# UART.net
KiCad netlist of a schematic drawn in Altium Designer
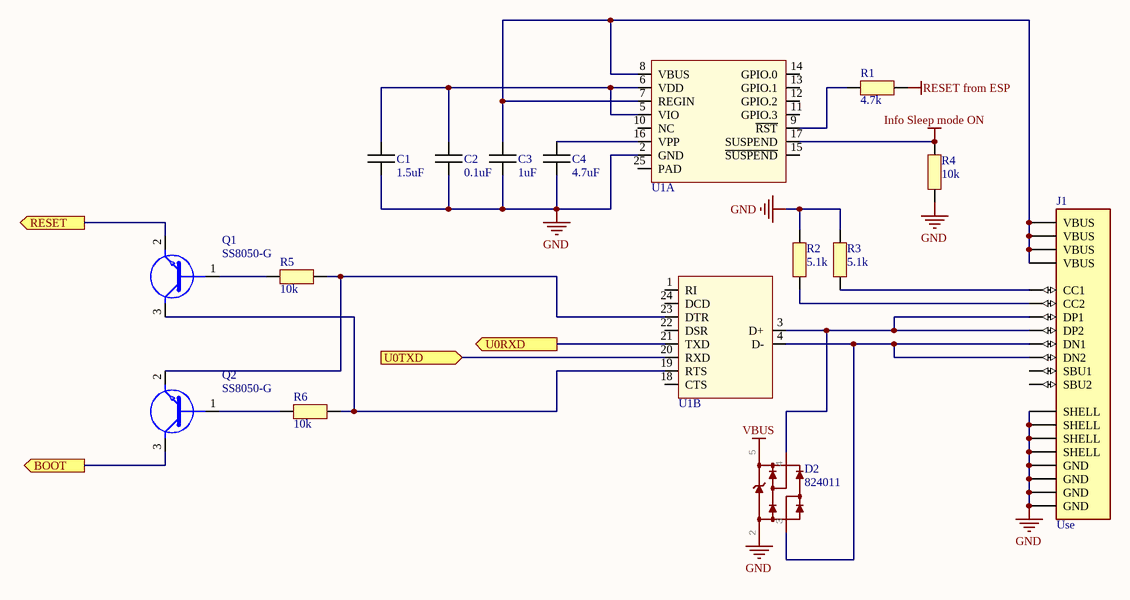
[diagram p0: UART.SchDoc]

(export (version "E")
  (design (tool "Eeschema 10.0.6"))
  (components
    (comp (ref "C1")
      (value "1.5uF")
      (footprint "CAPC1005X06N")
      (libsource (lib "SCHLibrary") (part "Capacitor"))
    )
    (comp (ref "C2")
      (value "0.1uF")
      (footprint "CAPC1005X06N")
      (libsource (lib "SCHLibrary") (part "Capacitor"))
    )
    (comp (ref "C3")
      (value "1uF")
      (footprint "CAPC1005X06N")
      (libsource (lib "SCHLibrary") (part "Capacitor"))
    )
    (comp (ref "C4")
      (value "4.7uF")
      (footprint "CAPC1005X06N")
      (libsource (lib "SCHLibrary") (part "Capacitor"))
    )
    (comp (ref "D2") (value "824011") (footprint "824011") (libsource (lib "SCHLibrary") (part "824011")))
    (comp (ref "J1")
      (value "Use")
      (footprint "USB4085-GF-A")
      (description "Connecteurs USB USB Type C, 2.0, Rec, TH , G/F, RA , Top Mnt, T & R")
      (libsource (lib "SCHLibrary") (part "USB4085-GF-A"))
    )
    (comp (ref "Q1")
      (value "SS8050-G")
      (footprint "SS8050-G")
      (description "Bipolar Transistors - BJT NPN TRANSISTOR 1.5A 40V")
      (libsource (lib "SCHLibrary") (part "SS8050-G"))
    )
    (comp (ref "Q2")
      (value "SS8050-G")
      (footprint "SS8050-G")
      (description "Bipolar Transistors - BJT NPN TRANSISTOR 1.5A 40V")
      (libsource (lib "SCHLibrary") (part "SS8050-G"))
    )
    (comp (ref "R1") (value "4.7k") (footprint "RESC1005X06N") (libsource (lib "") (part "Resistor_1")))
    (comp (ref "R2")
      (value "5.1k")
      (footprint "RESC1005X06N")
      (libsource (lib "SCHLibrary") (part "Resistor"))
    )
    (comp (ref "R3")
      (value "5.1k")
      (footprint "RESC1005X06N")
      (libsource (lib "SCHLibrary") (part "Resistor"))
    )
    (comp (ref "R4") (value "10k") (footprint "RESC1005X06N") (libsource (lib "") (part "Resistor_2")))
    (comp (ref "R5") (value "10k") (footprint "RESC1005X06N") (libsource (lib "") (part "Resistor_1")))
    (comp (ref "R6") (value "10k") (footprint "RESC1005X06N") (libsource (lib "") (part "Resistor_1")))
    (comp (ref "U1")
      (value "CP2104-F03-GM")
      (footprint "PQFN50P400X400X80_HS-25N")
      (description "USB Bridge, USB to UART USB 2.0 UART Interface 24-QFN (4x4)")
      (libsource (lib "SCHLibrary") (part "USBBridge"))
    )
  )
  (nets
    (net (code "1") (name "/BOOT") (class "Default")
      (node (ref "Q2") (pin "3") (pinfunction "C_3") (pintype "passive"))
    )
    (net (code "2") (name "/RESET") (class "Default")
      (node (ref "Q1") (pin "2") (pinfunction "E_2") (pintype "passive"))
    )
    (net (code "3") (name "/U0RXD") (class "Default")
      (node (ref "U1") (pin "21") (pinfunction "TXD_21") (pintype "passive"))
    )
    (net (code "4") (name "/U0TXD") (class "Default")
      (node (ref "U1") (pin "20") (pinfunction "RXD_20") (pintype "passive"))
    )
    (net (code "5") (name "GND") (class "Default")
      (node (ref "C1") (pin "2") (pinfunction "2_2") (pintype "passive"))
      (node (ref "C2") (pin "2") (pinfunction "2_2") (pintype "passive"))
      (node (ref "C3") (pin "2") (pinfunction "2_2") (pintype "passive"))
      (node (ref "C4") (pin "2") (pinfunction "2_2") (pintype "passive"))
      (node (ref "D2") (pin "2") (pinfunction "GND_2") (pintype "power_in"))
      (node (ref "J1") (pin "A1") (pinfunction "GND_A1") (pintype "power_in"))
      (node (ref "J1") (pin "A12") (pinfunction "GND_A12") (pintype "power_in"))
      (node (ref "J1") (pin "B1") (pinfunction "GND_B1") (pintype "power_in"))
      (node (ref "J1") (pin "B12") (pinfunction "GND_B12") (pintype "power_in"))
      (node (ref "J1") (pin "S1") (pinfunction "SHELL_S1") (pintype "passive"))
      (node (ref "J1") (pin "S2") (pinfunction "SHELL_S2") (pintype "passive"))
      (node (ref "J1") (pin "S3") (pinfunction "SHELL_S3") (pintype "passive"))
      (node (ref "J1") (pin "S4") (pinfunction "SHELL_S4") (pintype "passive"))
      (node (ref "R2") (pin "2") (pinfunction "2_2") (pintype "passive"))
      (node (ref "R3") (pin "2") (pinfunction "2_2") (pintype "passive"))
      (node (ref "R4") (pin "2") (pinfunction "2_2") (pintype "passive"))
      (node (ref "U1") (pin "2") (pinfunction "GND_2") (pintype "passive"))
    )
    (net (code "6") (name "Info Sleep mode ON") (class "Default")
      (node (ref "R4") (pin "1") (pinfunction "1_1") (pintype "passive"))
      (node (ref "U1") (pin "17") (pinfunction "SUSPEND_17") (pintype "passive"))
    )
    (net (code "7") (name "Net-(D2-1)") (class "Default")
      (node (ref "D2") (pin "3") (pinfunction "1_3") (pintype "passive"))
      (node (ref "J1") (pin "A7") (pinfunction "DN1_A7") (pintype "bidirectional"))
      (node (ref "J1") (pin "B7") (pinfunction "DN2_B7") (pintype "bidirectional"))
      (node (ref "U1") (pin "4") (pinfunction "D-_4") (pintype "passive"))
    )
    (net (code "8") (name "Net-(D2-2)") (class "Default")
      (node (ref "D2") (pin "4") (pinfunction "2_4") (pintype "passive"))
      (node (ref "J1") (pin "A6") (pinfunction "DP1_A6") (pintype "bidirectional"))
      (node (ref "J1") (pin "B6") (pinfunction "DP2_B6") (pintype "bidirectional"))
      (node (ref "U1") (pin "3") (pinfunction "D+_3") (pintype "passive"))
    )
    (net (code "9") (name "Net-(J1-CC1)") (class "Default")
      (node (ref "J1") (pin "A5") (pinfunction "CC1_A5") (pintype "bidirectional"))
      (node (ref "R3") (pin "1") (pinfunction "1_1") (pintype "passive"))
    )
    (net (code "10") (name "Net-(J1-CC2)") (class "Default")
      (node (ref "J1") (pin "B5") (pinfunction "CC2_B5") (pintype "bidirectional"))
      (node (ref "R2") (pin "1") (pinfunction "1_1") (pintype "passive"))
    )
    (net (code "11") (name "Net-(Q1-B)") (class "Default")
      (node (ref "Q1") (pin "1") (pinfunction "B_1") (pintype "passive"))
      (node (ref "R5") (pin "2") (pinfunction "2_2") (pintype "passive"))
    )
    (net (code "12") (name "Net-(Q1-C)") (class "Default")
      (node (ref "Q1") (pin "3") (pinfunction "C_3") (pintype "passive"))
      (node (ref "R6") (pin "1") (pinfunction "1_1") (pintype "passive"))
      (node (ref "U1") (pin "19") (pinfunction "RTS_19") (pintype "passive"))
    )
    (net (code "13") (name "Net-(Q2-B)") (class "Default")
      (node (ref "Q2") (pin "1") (pinfunction "B_1") (pintype "passive"))
      (node (ref "R6") (pin "2") (pinfunction "2_2") (pintype "passive"))
    )
    (net (code "14") (name "Net-(Q2-E)") (class "Default")
      (node (ref "Q2") (pin "2") (pinfunction "E_2") (pintype "passive"))
      (node (ref "R5") (pin "1") (pinfunction "1_1") (pintype "passive"))
      (node (ref "U1") (pin "23") (pinfunction "DTR_23") (pintype "passive"))
    )
    (net (code "15") (name "Net-(U1A-REGIN)") (class "Default")
      (node (ref "C3") (pin "1") (pinfunction "1_1") (pintype "passive"))
      (node (ref "J1") (pin "A4") (pinfunction "VBUS_A4") (pintype "power_in"))
      (node (ref "J1") (pin "A9") (pinfunction "VBUS_A9") (pintype "power_in"))
      (node (ref "J1") (pin "B4") (pinfunction "VBUS_B4") (pintype "power_in"))
      (node (ref "J1") (pin "B9") (pinfunction "VBUS_B9") (pintype "power_in"))
      (node (ref "U1") (pin "7") (pinfunction "REGIN_7") (pintype "passive"))
      (node (ref "U1") (pin "8") (pinfunction "VBUS_8") (pintype "passive"))
    )
    (net (code "16") (name "Net-(U1A-VDD)") (class "Default")
      (node (ref "C1") (pin "1") (pinfunction "1_1") (pintype "passive"))
      (node (ref "C2") (pin "1") (pinfunction "1_1") (pintype "passive"))
      (node (ref "U1") (pin "5") (pinfunction "VIO_5") (pintype "passive"))
      (node (ref "U1") (pin "6") (pinfunction "VDD_6") (pintype "passive"))
    )
    (net (code "17") (name "Net-(U1A-VPP)") (class "Default")
      (node (ref "C4") (pin "1") (pinfunction "1_1") (pintype "passive"))
      (node (ref "U1") (pin "16") (pinfunction "VPP_16") (pintype "passive"))
    )
    (net (code "18") (name "Net-(U1A-~{RST})") (class "Default")
      (node (ref "R1") (pin "2") (pinfunction "2_2") (pintype "passive"))
      (node (ref "U1") (pin "9") (pinfunction "~{RST}_9") (pintype "passive"))
    )
    (net (code "19") (name "RESET from ESP") (class "Default")
      (node (ref "R1") (pin "1") (pinfunction "1_1") (pintype "passive"))
    )
    (net (code "20") (name "VBUS") (class "Default")
      (node (ref "D2") (pin "5") (pinfunction "VDD_5") (pintype "power_in"))
    )
    (net (code "21") (name "unconnected-(J1-SBU1-PadA8)") (class "Default")
      (node (ref "J1") (pin "A8") (pinfunction "SBU1_A8") (pintype "bidirectional"))
    )
    (net (code "22") (name "unconnected-(J1-SBU2-PadB8)") (class "Default")
      (node (ref "J1") (pin "B8") (pinfunction "SBU2_B8") (pintype "bidirectional"))
    )
    (net (code "23") (name "unconnected-(U1A-GPIO.0-Pad14)") (class "Default")
      (node (ref "U1") (pin "14") (pinfunction "GPIO.0_14") (pintype "passive"))
    )
    (net (code "24") (name "unconnected-(U1A-GPIO.1-Pad13)") (class "Default")
      (node (ref "U1") (pin "13") (pinfunction "GPIO.1_13") (pintype "passive"))
    )
    (net (code "25") (name "unconnected-(U1A-GPIO.2-Pad12)") (class "Default")
      (node (ref "U1") (pin "12") (pinfunction "GPIO.2_12") (pintype "passive"))
    )
    (net (code "26") (name "unconnected-(U1A-GPIO.3-Pad11)") (class "Default")
      (node (ref "U1") (pin "11") (pinfunction "GPIO.3_11") (pintype "passive"))
    )
    (net (code "27") (name "unconnected-(U1A-NC-Pad10)") (class "Default")
      (node (ref "U1") (pin "10") (pinfunction "NC_10") (pintype "passive"))
    )
    (net (code "28") (name "unconnected-(U1A-PAD-Pad25)") (class "Default")
      (node (ref "U1") (pin "25") (pinfunction "PAD_25") (pintype "passive"))
    )
    (net (code "29") (name "unconnected-(U1A-~{SUSPEND}-Pad15)") (class "Default")
      (node (ref "U1") (pin "15") (pinfunction "~{SUSPEND}_15") (pintype "passive"))
    )
    (net (code "30") (name "unconnected-(U1B-CTS-Pad18)") (class "Default")
      (node (ref "U1") (pin "18") (pinfunction "CTS_18") (pintype "passive"))
    )
    (net (code "31") (name "unconnected-(U1B-DCD-Pad24)") (class "Default")
      (node (ref "U1") (pin "24") (pinfunction "DCD_24") (pintype "passive"))
    )
    (net (code "32") (name "unconnected-(U1B-DSR-Pad22)") (class "Default")
      (node (ref "U1") (pin "22") (pinfunction "DSR_22") (pintype "passive"))
    )
    (net (code "33") (name "unconnected-(U1B-RI-Pad1)") (class "Default")
      (node (ref "U1") (pin "1") (pinfunction "RI_1") (pintype "passive"))
    )
  )
)
